# RF_AMP.net
KiCad netlist of a schematic drawn in Altium Designer
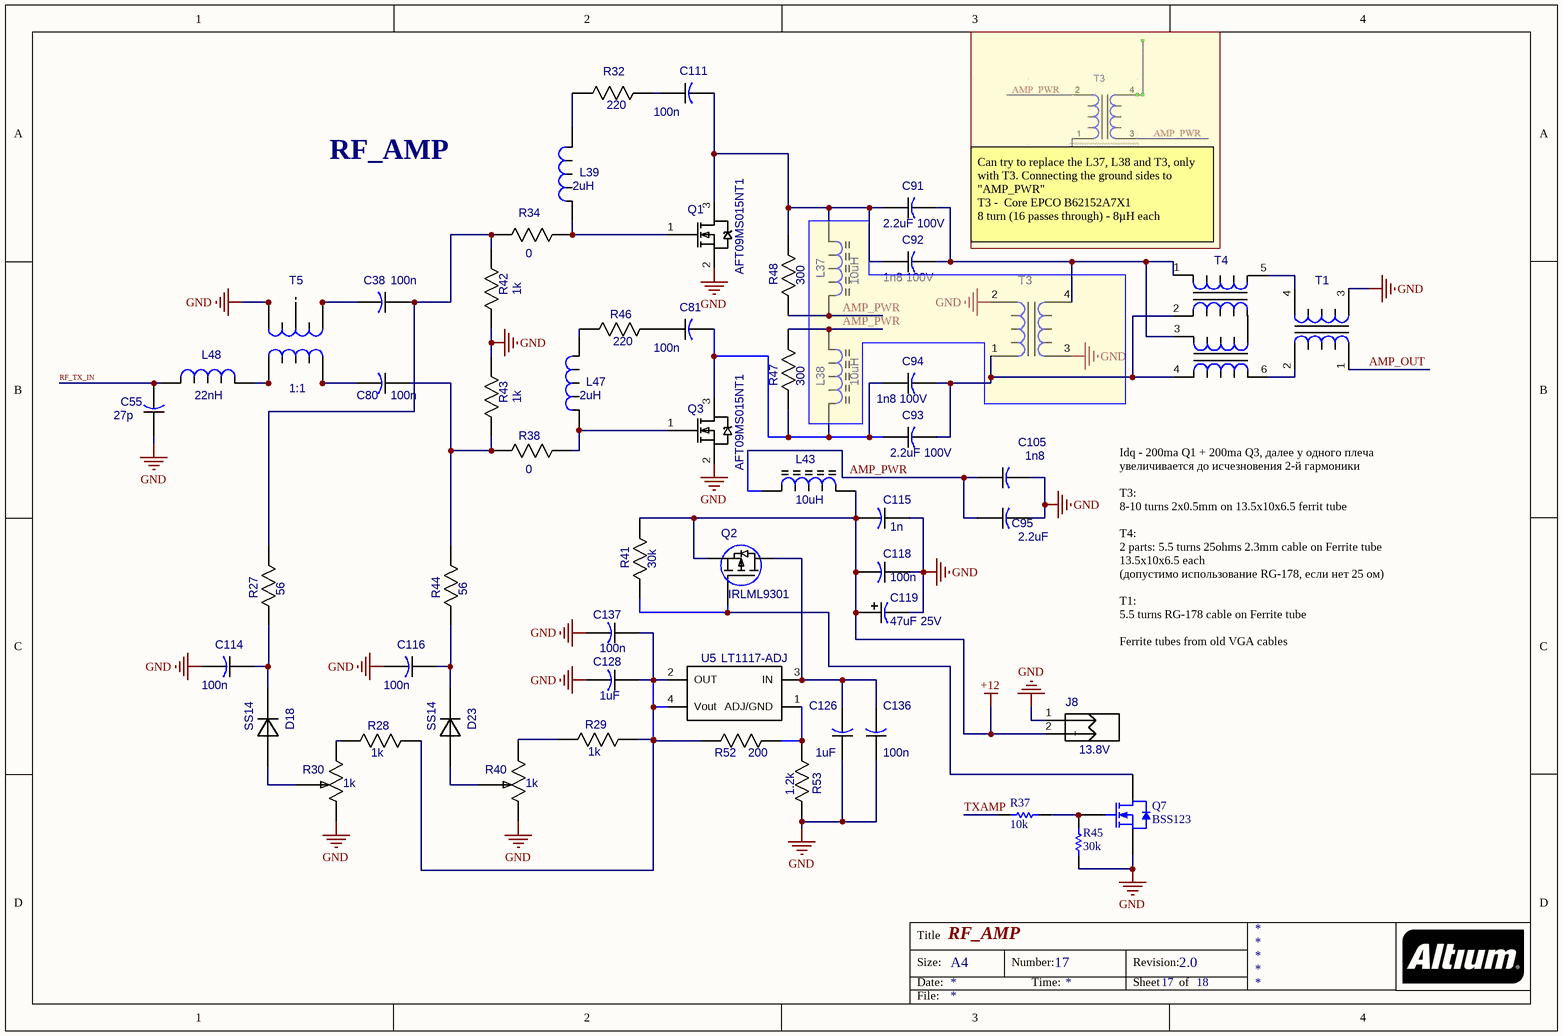
[diagram p0: RF_AMP.SchDoc]

(export (version "E")
  (design (tool "Eeschema 10.0.6"))
  (components
    (comp (ref "C38")
      (value "100n")
      (footprint "CAP_0805")
      (description "CAP_0805")
      (libsource (lib "*") (part "CAP_0805"))
    )
    (comp (ref "C55")
      (value "27p")
      (footprint "CAP_0805")
      (description "CAP_0805")
      (libsource (lib "*") (part "CAP_0805"))
    )
    (comp (ref "C80")
      (value "100n")
      (footprint "CAP_0805")
      (description "CAP_0805")
      (libsource (lib "*") (part "CAP_0805"))
    )
    (comp (ref "C81")
      (value "100n")
      (footprint "CAP_1206")
      (description "CAP_1206")
      (libsource (lib "*") (part "CAP_1206"))
    )
    (comp (ref "C91")
      (value "2.2uF 100V")
      (footprint "CAP_1206")
      (description "CAP_1206")
      (libsource (lib "*") (part "CAP_1206"))
    )
    (comp (ref "C92")
      (value "1n8 100V")
      (footprint "CAP_1206")
      (description "CAP_1206")
      (libsource (lib "*") (part "CAP_1206"))
    )
    (comp (ref "C93")
      (value "2.2uF 100V")
      (footprint "CAP_1206")
      (description "CAP_1206")
      (libsource (lib "*") (part "CAP_1206"))
    )
    (comp (ref "C94")
      (value "1n8 100V")
      (footprint "CAP_1206")
      (description "CAP_1206")
      (libsource (lib "*") (part "CAP_1206"))
    )
    (comp (ref "C95")
      (value "2.2uF")
      (footprint "CAP_1206")
      (description "CAP_1206")
      (libsource (lib "*") (part "CAP_1206"))
    )
    (comp (ref "C105")
      (value "1n8")
      (footprint "CAP_1206")
      (description "CAP_1206")
      (libsource (lib "*") (part "CAP_1206"))
    )
    (comp (ref "C111")
      (value "100n")
      (footprint "CAP_1206")
      (description "CAP_1206")
      (libsource (lib "*") (part "CAP_1206"))
    )
    (comp (ref "C114")
      (value "100n")
      (footprint "CAP_0805")
      (description "CAP_0805")
      (libsource (lib "*") (part "CAP_0805"))
    )
    (comp (ref "C115")
      (value "1n")
      (footprint "CAP_0805")
      (description "CAP_0805")
      (libsource (lib "*") (part "CAP_0805"))
    )
    (comp (ref "C116")
      (value "100n")
      (footprint "CAP_0805")
      (description "CAP_0805")
      (libsource (lib "*") (part "CAP_0805"))
    )
    (comp (ref "C118")
      (value "100n")
      (footprint "CAP_0805")
      (description "CAP_0805")
      (libsource (lib "*") (part "CAP_0805"))
    )
    (comp (ref "C119")
      (value "47uF 25V")
      (footprint "CAPAE_6.6x6.6h5.4")
      (description "CAPAE_6.6x6.6h5.4")
      (libsource (lib "*") (part "CAPAE_6.6x6.6h5.4"))
    )
    (comp (ref "C126")
      (value "1uF")
      (footprint "CAP_0805")
      (description "CAP_0805")
      (libsource (lib "*") (part "CAP_0805"))
    )
    (comp (ref "C128")
      (value "1uF")
      (footprint "CAP_0805")
      (description "CAP_0805")
      (libsource (lib "*") (part "CAP_0805"))
    )
    (comp (ref "C136")
      (value "100n")
      (footprint "CAP_0805")
      (description "CAP_0805")
      (libsource (lib "*") (part "CAP_0805"))
    )
    (comp (ref "C137")
      (value "100n")
      (footprint "CAP_0805")
      (description "CAP_0805")
      (libsource (lib "*") (part "CAP_0805"))
    )
    (comp (ref "D18") (value "SS14") (footprint "SS14") (libsource (lib "*") (part "SS14")))
    (comp (ref "D23") (value "SS14") (footprint "SS14") (libsource (lib "*") (part "SS14")))
    (comp (ref "J8")
      (value "13.8V")
      (footprint "1986717-2")
      (description "JX2")
      (libsource (lib "*") (part "1986717-2"))
    )
    (comp (ref "L37")
      (value "10uH")
      (footprint "IND_FERRITE_CORE")
      (description "Inductor")
      (libsource (lib "*") (part "IND_FERRITE_CORE"))
    )
    (comp (ref "L38")
      (value "10uH")
      (footprint "IND_FERRITE_CORE")
      (description "Inductor")
      (libsource (lib "*") (part "IND_FERRITE_CORE"))
    )
    (comp (ref "L39")
      (value "2uH")
      (footprint "IND_0805")
      (description "IND_0805")
      (libsource (lib "*") (part "IND_0805"))
    )
    (comp (ref "L43")
      (value "10uH")
      (footprint "IND_FERRITE_CORE")
      (description "Inductor")
      (libsource (lib "*") (part "IND_FERRITE_CORE"))
    )
    (comp (ref "L47")
      (value "2uH")
      (footprint "IND_0805")
      (description "IND_0805")
      (libsource (lib "*") (part "IND_0805"))
    )
    (comp (ref "L48")
      (value "22nH")
      (footprint "IND_0805")
      (description "IND_0805")
      (libsource (lib "*") (part "IND_0805"))
    )
    (comp (ref "Q1")
      (value "AFT09MS015NT1")
      (footprint "AFT09MS015NT1")
      (libsource (lib "RF-UNIT-QRP") (part "AFT09MS015NT1"))
    )
    (comp (ref "Q2")
      (value "IRLML9301")
      (footprint "SOT23")
      (description "MOSFET")
      (libsource (lib "*") (part "MOSFET_ENH_PD"))
    )
    (comp (ref "Q3")
      (value "AFT09MS015NT1")
      (footprint "AFT09MS015NT1")
      (libsource (lib "RF-UNIT-QRP") (part "AFT09MS015NT1"))
    )
    (comp (ref "Q7")
      (value "BSS123")
      (footprint "FAIR-SOT23-3_V")
      (fields (field (name "MANUFACTURER") "Fairchild"))
      (libsource (lib "Altium Content Vault") (part "NEMOS-GSD-3"))
    )
    (comp (ref "R27")
      (value "56")
      (footprint "RES_0805")
      (description "RES_0805")
      (libsource (lib "*") (part "RES_0805"))
    )
    (comp (ref "R28")
      (value "1k")
      (footprint "RES_0805")
      (description "RES_0805")
      (libsource (lib "*") (part "RES_0805"))
    )
    (comp (ref "R29")
      (value "1k")
      (footprint "RES_0805")
      (description "RES_0805")
      (libsource (lib "*") (part "RES_0805"))
    )
    (comp (ref "R30")
      (value "1k")
      (footprint "306J")
      (description "306J")
      (fields (field (name "Comment") "ADJ-1k"))
      (libsource (lib "*") (part "306J"))
    )
    (comp (ref "R32")
      (value "220")
      (footprint "RES_0805")
      (description "RES_0805")
      (libsource (lib "*") (part "RES_0805"))
    )
    (comp (ref "R34")
      (value "0")
      (footprint "RES_1206")
      (description "RES_1206")
      (libsource (lib "*") (part "RES_1206"))
    )
    (comp (ref "R37")
      (value "10k")
      (footprint "RESC2013X60X40NL20T25")
      (description "RES_0805")
      (fields (field (name "MANUFACTURER") "Panasonic") (field (name "PART NUMBER") "ERA-6AEB303V"))
      (libsource (lib "Altium Content Vault") (part "RES"))
    )
    (comp (ref "R38")
      (value "0")
      (footprint "RES_1206")
      (description "RES_1206")
      (libsource (lib "*") (part "RES_1206"))
    )
    (comp (ref "R40")
      (value "1k")
      (footprint "306J")
      (description "306J")
      (fields (field (name "Comment") "ADJ-1k"))
      (libsource (lib "*") (part "306J"))
    )
    (comp (ref "R41")
      (value "30k")
      (footprint "RES_0805")
      (description "RES_0805")
      (libsource (lib "*") (part "RES_0805"))
    )
    (comp (ref "R42")
      (value "1k")
      (footprint "RES_0805")
      (description "RES_0805")
      (libsource (lib "*") (part "RES_0805"))
    )
    (comp (ref "R43")
      (value "1k")
      (footprint "RES_0805")
      (description "RES_0805")
      (libsource (lib "*") (part "RES_0805"))
    )
    (comp (ref "R44")
      (value "56")
      (footprint "RES_0805")
      (description "RES_0805")
      (libsource (lib "*") (part "RES_0805"))
    )
    (comp (ref "R45")
      (value "30k")
      (footprint "RESC2013X60X40NL20T25")
      (description "RES_0805")
      (fields (field (name "MANUFACTURER") "Panasonic") (field (name "PART NUMBER") "ERA-6AEB303V"))
      (libsource (lib "Altium Content Vault") (part "RES"))
    )
    (comp (ref "R46")
      (value "220")
      (footprint "RES_0805")
      (description "RES_0805")
      (libsource (lib "*") (part "RES_0805"))
    )
    (comp (ref "R47")
      (value "300")
      (footprint "RES_1206")
      (description "RES_1206")
      (libsource (lib "*") (part "RES_1206"))
    )
    (comp (ref "R48")
      (value "300")
      (footprint "RES_1206")
      (description "RES_1206")
      (libsource (lib "*") (part "RES_1206"))
    )
    (comp (ref "R52")
      (value "200")
      (footprint "RES_0805")
      (description "RES_0805")
      (libsource (lib "*") (part "RES_0805"))
    )
    (comp (ref "R53")
      (value "1.2k")
      (footprint "RES_0805")
      (description "RES_0805")
      (libsource (lib "*") (part "RES_0805"))
    )
    (comp (ref "T1")
      (value "8T M2000HM 10*6*5")
      (footprint "Rutrof 2")
      (description "Transformer")
      (libsource (lib "*") (part "TRANSF_ICORE"))
    )
    (comp (ref "T3")
      (value "8T M2000HM 10*6*5")
      (footprint "Rutrof")
      (description "Transformer")
      (libsource (lib "*") (part "TRANSF_ICORE"))
    )
    (comp (ref "T4")
      (value "TRANSF_OUT")
      (footprint "TRANSF_OUT")
      (libsource (lib "RF-UNIT") (part "TRANSF_OUT_2"))
    )
    (comp (ref "T5")
      (value "1:1")
      (footprint "TRANSF_ACORE2")
      (libsource (lib "RF-UNIT_1") (part "TRANSF_ACORE2"))
    )
    (comp (ref "U5")
      (value "LT1117-ADJ")
      (footprint "LT1117IST-ADJ")
      (description "LT1117IST-ADJ")
      (libsource (lib "*") (part "LT1117IST-ADJ"))
    )
  )
  (nets
    (net (code "1") (name "+12") (class "Default")
      (node (ref "C115") (pin "2") (pinfunction "2_2") (pintype "passive"))
      (node (ref "C118") (pin "2") (pinfunction "2_2") (pintype "passive"))
      (node (ref "C119") (pin "1") (pinfunction "PLUS_1") (pintype "passive"))
      (node (ref "J8") (pin "2") (pinfunction "+_2") (pintype "passive"))
      (node (ref "L43") (pin "2") (pinfunction "B_2") (pintype "passive"))
      (node (ref "Q2") (pin "2") (pinfunction "S_2") (pintype "passive"))
      (node (ref "R41") (pin "2") (pinfunction "2_2") (pintype "passive"))
    )
    (net (code "2") (name "/AMP_OUT") (class "Default")
      (node (ref "T1") (pin "1") (pinfunction "P1_1") (pintype "passive"))
    )
    (net (code "3") (name "/AMP_PWR") (class "Default")
      (node (ref "C105") (pin "1") (pinfunction "1_1") (pintype "passive"))
      (node (ref "C95") (pin "1") (pinfunction "1_1") (pintype "passive"))
      (node (ref "L37") (pin "2") (pinfunction "B_2") (pintype "passive"))
      (node (ref "L38") (pin "1") (pinfunction "A_1") (pintype "passive"))
      (node (ref "L43") (pin "1") (pinfunction "A_1") (pintype "passive"))
      (node (ref "R47") (pin "2") (pinfunction "2_2") (pintype "passive"))
      (node (ref "R48") (pin "1") (pinfunction "1_1") (pintype "passive"))
    )
    (net (code "4") (name "/RF_TX_IN") (class "Default")
      (node (ref "C55") (pin "2") (pinfunction "2_2") (pintype "passive"))
      (node (ref "L48") (pin "1") (pinfunction "1_1") (pintype "passive"))
    )
    (net (code "5") (name "/TXAMP") (class "Default")
      (node (ref "R37") (pin "2") (pinfunction "2_2") (pintype "passive"))
    )
    (net (code "6") (name "GND") (class "Default")
      (node (ref "C105") (pin "2") (pinfunction "2_2") (pintype "passive"))
      (node (ref "C114") (pin "2") (pinfunction "2_2") (pintype "passive"))
      (node (ref "C115") (pin "1") (pinfunction "1_1") (pintype "passive"))
      (node (ref "C116") (pin "2") (pinfunction "2_2") (pintype "passive"))
      (node (ref "C118") (pin "1") (pinfunction "1_1") (pintype "passive"))
      (node (ref "C119") (pin "2") (pinfunction "MINUS_2") (pintype "passive"))
      (node (ref "C126") (pin "1") (pinfunction "1_1") (pintype "passive"))
      (node (ref "C128") (pin "2") (pinfunction "2_2") (pintype "passive"))
      (node (ref "C136") (pin "1") (pinfunction "1_1") (pintype "passive"))
      (node (ref "C137") (pin "2") (pinfunction "2_2") (pintype "passive"))
      (node (ref "C55") (pin "1") (pinfunction "1_1") (pintype "passive"))
      (node (ref "C95") (pin "2") (pinfunction "2_2") (pintype "passive"))
      (node (ref "J8") (pin "1") (pinfunction "-_1") (pintype "passive"))
      (node (ref "Q1") (pin "2") (pinfunction "S_2") (pintype "passive"))
      (node (ref "Q3") (pin "2") (pinfunction "S_2") (pintype "passive"))
      (node (ref "Q7") (pin "2") (pinfunction "S_2") (pintype "passive"))
      (node (ref "R30") (pin "1") (pinfunction "CCW_1") (pintype "passive"))
      (node (ref "R40") (pin "1") (pinfunction "CCW_1") (pintype "passive"))
      (node (ref "R42") (pin "1") (pinfunction "1_1") (pintype "passive"))
      (node (ref "R43") (pin "2") (pinfunction "2_2") (pintype "passive"))
      (node (ref "R45") (pin "1") (pinfunction "1_1") (pintype "passive"))
      (node (ref "R53") (pin "2") (pinfunction "2_2") (pintype "passive"))
      (node (ref "T1") (pin "3") (pinfunction "S1_3") (pintype "passive"))
      (node (ref "T3") (pin "2") (pinfunction "P2_2") (pintype "passive"))
      (node (ref "T3") (pin "3") (pinfunction "S1_3") (pintype "passive"))
      (node (ref "T5") (pin "3") (pinfunction "S3_3") (pintype "passive"))
      (node (ref "T5") (pin "9") (pinfunction "0_9") (pintype "passive"))
    )
    (net (code "7") (name "Net-(C38-Pad1)") (class "Default")
      (node (ref "C38") (pin "1") (pinfunction "1_1") (pintype "passive"))
      (node (ref "R27") (pin "2") (pinfunction "2_2") (pintype "passive"))
      (node (ref "R34") (pin "1") (pinfunction "1_1") (pintype "passive"))
      (node (ref "R42") (pin "2") (pinfunction "2_2") (pintype "passive"))
    )
    (net (code "8") (name "Net-(C80-Pad1)") (class "Default")
      (node (ref "C80") (pin "1") (pinfunction "1_1") (pintype "passive"))
      (node (ref "R38") (pin "1") (pinfunction "1_1") (pintype "passive"))
      (node (ref "R43") (pin "1") (pinfunction "1_1") (pintype "passive"))
      (node (ref "R44") (pin "2") (pinfunction "2_2") (pintype "passive"))
    )
    (net (code "9") (name "Net-(C81-Pad1)") (class "Default")
      (node (ref "C81") (pin "1") (pinfunction "1_1") (pintype "passive"))
      (node (ref "R46") (pin "2") (pinfunction "2_2") (pintype "passive"))
    )
    (net (code "10") (name "Net-(C111-Pad1)") (class "Default")
      (node (ref "C111") (pin "1") (pinfunction "1_1") (pintype "passive"))
      (node (ref "R32") (pin "2") (pinfunction "2_2") (pintype "passive"))
    )
    (net (code "11") (name "Net-(D18-A)") (class "Default")
      (node (ref "D18") (pin "2") (pinfunction "A_2") (pintype "passive"))
      (node (ref "R30") (pin "2") (pinfunction "W_2") (pintype "passive"))
    )
    (net (code "12") (name "Net-(D18-K)") (class "Default")
      (node (ref "C114") (pin "1") (pinfunction "1_1") (pintype "passive"))
      (node (ref "D18") (pin "1") (pinfunction "K_1") (pintype "passive"))
      (node (ref "R27") (pin "1") (pinfunction "1_1") (pintype "passive"))
    )
    (net (code "13") (name "Net-(D23-A)") (class "Default")
      (node (ref "D23") (pin "2") (pinfunction "A_2") (pintype "passive"))
      (node (ref "R40") (pin "2") (pinfunction "W_2") (pintype "passive"))
    )
    (net (code "14") (name "Net-(D23-K)") (class "Default")
      (node (ref "C116") (pin "1") (pinfunction "1_1") (pintype "passive"))
      (node (ref "D23") (pin "1") (pinfunction "K_1") (pintype "passive"))
      (node (ref "R44") (pin "1") (pinfunction "1_1") (pintype "passive"))
    )
    (net (code "15") (name "Net-(L37-A)") (class "Default")
      (node (ref "C111") (pin "2") (pinfunction "2_2") (pintype "passive"))
      (node (ref "C91") (pin "1") (pinfunction "1_1") (pintype "passive"))
      (node (ref "C92") (pin "1") (pinfunction "1_1") (pintype "passive"))
      (node (ref "L37") (pin "1") (pinfunction "A_1") (pintype "passive"))
      (node (ref "Q1") (pin "3") (pinfunction "D_3") (pintype "passive"))
      (node (ref "R48") (pin "2") (pinfunction "2_2") (pintype "passive"))
    )
    (net (code "16") (name "Net-(L38-B)") (class "Default")
      (node (ref "C81") (pin "2") (pinfunction "2_2") (pintype "passive"))
      (node (ref "C93") (pin "1") (pinfunction "1_1") (pintype "passive"))
      (node (ref "C94") (pin "1") (pinfunction "1_1") (pintype "passive"))
      (node (ref "L38") (pin "2") (pinfunction "B_2") (pintype "passive"))
      (node (ref "Q3") (pin "3") (pinfunction "D_3") (pintype "passive"))
      (node (ref "R47") (pin "1") (pinfunction "1_1") (pintype "passive"))
    )
    (net (code "17") (name "Net-(L39-Pad2)") (class "Default")
      (node (ref "L39") (pin "2") (pinfunction "2_2") (pintype "passive"))
      (node (ref "R32") (pin "1") (pinfunction "1_1") (pintype "passive"))
    )
    (net (code "18") (name "Net-(L47-Pad2)") (class "Default")
      (node (ref "L47") (pin "2") (pinfunction "2_2") (pintype "passive"))
      (node (ref "R46") (pin "1") (pinfunction "1_1") (pintype "passive"))
    )
    (net (code "19") (name "Net-(Q1-G)") (class "Default")
      (node (ref "L39") (pin "1") (pinfunction "1_1") (pintype "passive"))
      (node (ref "Q1") (pin "1") (pinfunction "G_1") (pintype "passive"))
      (node (ref "R34") (pin "2") (pinfunction "2_2") (pintype "passive"))
    )
    (net (code "20") (name "Net-(Q2-D)") (class "Default")
      (node (ref "C126") (pin "2") (pinfunction "2_2") (pintype "passive"))
      (node (ref "C136") (pin "2") (pinfunction "2_2") (pintype "passive"))
      (node (ref "Q2") (pin "3") (pinfunction "D_3") (pintype "passive"))
      (node (ref "U5") (pin "3") (pinfunction "IN_3") (pintype "passive"))
    )
    (net (code "21") (name "Net-(Q2-G)") (class "Default")
      (node (ref "Q2") (pin "1") (pinfunction "G_1") (pintype "passive"))
      (node (ref "Q7") (pin "3") (pinfunction "D_3") (pintype "passive"))
      (node (ref "R41") (pin "1") (pinfunction "1_1") (pintype "passive"))
    )
    (net (code "22") (name "Net-(Q3-G)") (class "Default")
      (node (ref "L47") (pin "1") (pinfunction "1_1") (pintype "passive"))
      (node (ref "Q3") (pin "1") (pinfunction "G_1") (pintype "passive"))
      (node (ref "R38") (pin "2") (pinfunction "2_2") (pintype "passive"))
    )
    (net (code "23") (name "Net-(Q7-G)") (class "Default")
      (node (ref "Q7") (pin "1") (pinfunction "G_1") (pintype "passive"))
      (node (ref "R37") (pin "1") (pinfunction "1_1") (pintype "passive"))
      (node (ref "R45") (pin "2") (pinfunction "2_2") (pintype "passive"))
    )
    (net (code "24") (name "Net-(R30-CW)") (class "Default")
      (node (ref "R28") (pin "1") (pinfunction "1_1") (pintype "passive"))
      (node (ref "R30") (pin "3") (pinfunction "CW_3") (pintype "passive"))
    )
    (net (code "25") (name "Net-(R40-CW)") (class "Default")
      (node (ref "R29") (pin "1") (pinfunction "1_1") (pintype "passive"))
      (node (ref "R40") (pin "3") (pinfunction "CW_3") (pintype "passive"))
    )
    (net (code "26") (name "Net-(T1-P2)") (class "Default")
      (node (ref "T1") (pin "2") (pinfunction "P2_2") (pintype "passive"))
      (node (ref "T4") (pin "6") (pinfunction "OUT2_6") (pintype "passive"))
    )
    (net (code "27") (name "Net-(T1-S2)") (class "Default")
      (node (ref "T1") (pin "4") (pinfunction "S2_4") (pintype "passive"))
      (node (ref "T4") (pin "5") (pinfunction "OUT1_5") (pintype "passive"))
    )
    (net (code "28") (name "Net-(T3-P1)") (class "Default")
      (node (ref "C93") (pin "2") (pinfunction "2_2") (pintype "passive"))
      (node (ref "C94") (pin "2") (pinfunction "2_2") (pintype "passive"))
      (node (ref "T3") (pin "1") (pinfunction "P1_1") (pintype "passive"))
      (node (ref "T4") (pin "2") (pinfunction "T1N_2") (pintype "passive"))
      (node (ref "T4") (pin "4") (pinfunction "T2P_4") (pintype "passive"))
    )
    (net (code "29") (name "Net-(T3-S2)") (class "Default")
      (node (ref "C91") (pin "2") (pinfunction "2_2") (pintype "passive"))
      (node (ref "C92") (pin "2") (pinfunction "2_2") (pintype "passive"))
      (node (ref "T3") (pin "4") (pinfunction "S2_4") (pintype "passive"))
      (node (ref "T4") (pin "1") (pinfunction "T1P_1") (pintype "passive"))
      (node (ref "T4") (pin "3") (pinfunction "T2N_3") (pintype "passive"))
    )
    (net (code "30") (name "Net-(T5-P1)") (class "Default")
      (node (ref "C80") (pin "2") (pinfunction "2_2") (pintype "passive"))
      (node (ref "T5") (pin "10") (pinfunction "0_10") (pintype "passive"))
      (node (ref "T5") (pin "6") (pinfunction "P1_6") (pintype "passive"))
    )
    (net (code "31") (name "Net-(T5-P2)") (class "Default")
      (node (ref "L48") (pin "2") (pinfunction "2_2") (pintype "passive"))
      (node (ref "T5") (pin "11") (pinfunction "0_11") (pintype "passive"))
      (node (ref "T5") (pin "4") (pinfunction "P2_4") (pintype "passive"))
    )
    (net (code "32") (name "Net-(T5-S1)") (class "Default")
      (node (ref "C38") (pin "2") (pinfunction "2_2") (pintype "passive"))
      (node (ref "T5") (pin "1") (pinfunction "S1_1") (pintype "passive"))
      (node (ref "T5") (pin "7") (pinfunction "0_7") (pintype "passive"))
    )
    (net (code "33") (name "Net-(U5-ADJ{slash}GND)") (class "Default")
      (node (ref "R52") (pin "2") (pinfunction "2_2") (pintype "passive"))
      (node (ref "R53") (pin "1") (pinfunction "1_1") (pintype "passive"))
      (node (ref "U5") (pin "1") (pinfunction "ADJ/GND_1") (pintype "passive"))
    )
    (net (code "34") (name "Net-(U5-OUT)") (class "Default")
      (node (ref "C128") (pin "1") (pinfunction "1_1") (pintype "passive"))
      (node (ref "C137") (pin "1") (pinfunction "1_1") (pintype "passive"))
      (node (ref "R28") (pin "2") (pinfunction "2_2") (pintype "passive"))
      (node (ref "R29") (pin "2") (pinfunction "2_2") (pintype "passive"))
      (node (ref "R52") (pin "1") (pinfunction "1_1") (pintype "passive"))
      (node (ref "U5") (pin "2") (pinfunction "OUT_2") (pintype "passive"))
      (node (ref "U5") (pin "4") (pinfunction "Vout_4") (pintype "passive"))
    )
    (net (code "35") (name "unconnected-(T5-S2-Pad2)") (class "Default")
      (node (ref "T5") (pin "2") (pinfunction "S2_2") (pintype "passive"))
    )
    (net (code "36") (name "unconnected-(T5-S2-Pad8)") (class "Default")
      (node (ref "T5") (pin "8") (pinfunction "S2_8") (pintype "passive"))
    )
  )
)
